# RemoteBoard.net
KiCad netlist of a schematic drawn in EAGLE
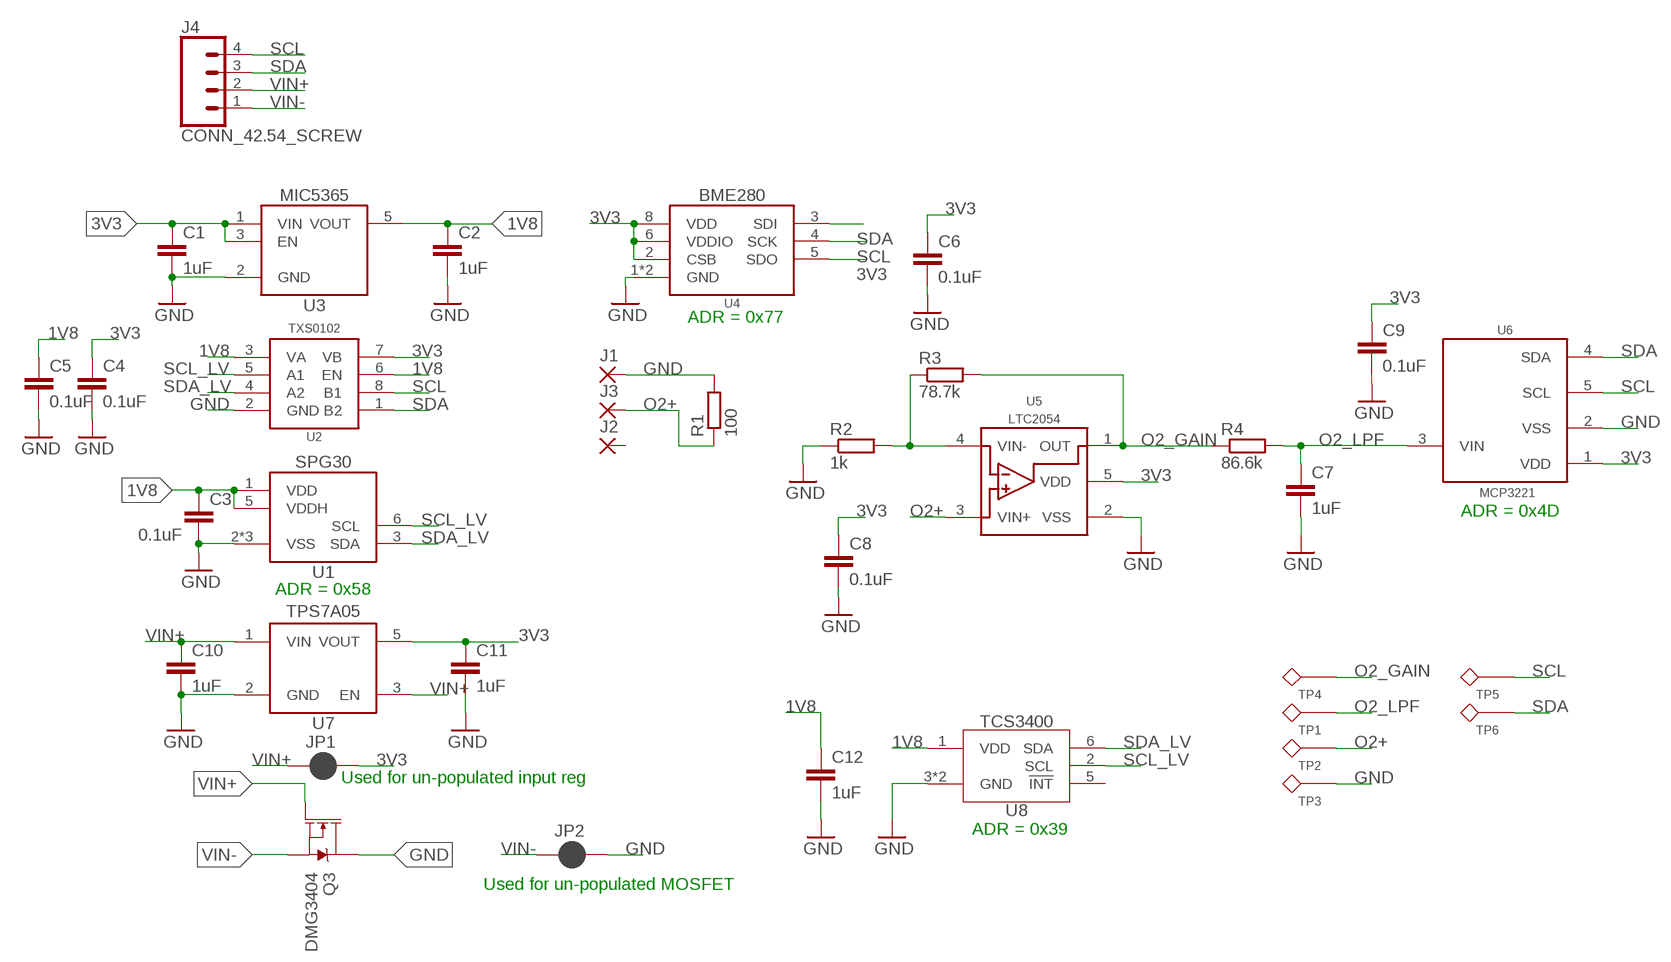
[diagram p0: schematic, sheet 1]

(export (version "E")
  (design (tool "Eeschema 10.0.6"))
  (components
    (comp (ref "C1")
      (value "1uF")
      (footprint "eagle-import:C0805")
      (fields (field (name "MF") "Yageo") (field (name "MPN") "CC0805KKX7R8BB105"))
      (libsource (lib "eagle-import") (part "C-EUC08051UF"))
    )
    (comp (ref "C2")
      (value "1uF")
      (footprint "eagle-import:C0805")
      (fields (field (name "MF") "Yageo") (field (name "MPN") "CC0805KKX7R8BB105"))
      (libsource (lib "eagle-import") (part "C-EUC08051UF"))
    )
    (comp (ref "C3")
      (value "0.1uF")
      (footprint "eagle-import:C0805")
      (fields (field (name "MF") "Kemet") (field (name "MPN") "C0805C104M3RACTU"))
      (libsource (lib "eagle-import") (part "C-EUC08050.1UF"))
    )
    (comp (ref "C4")
      (value "0.1uF")
      (footprint "eagle-import:C0805")
      (fields (field (name "MF") "Kemet") (field (name "MPN") "C0805C104M3RACTU"))
      (libsource (lib "eagle-import") (part "C-EUC08050.1UF"))
    )
    (comp (ref "C5")
      (value "0.1uF")
      (footprint "eagle-import:C0805")
      (fields (field (name "MF") "Kemet") (field (name "MPN") "C0805C104M3RACTU"))
      (libsource (lib "eagle-import") (part "C-EUC08050.1UF"))
    )
    (comp (ref "C6")
      (value "0.1uF")
      (footprint "eagle-import:C0805")
      (fields (field (name "MF") "Kemet") (field (name "MPN") "C0805C104M3RACTU"))
      (libsource (lib "eagle-import") (part "C-EUC08050.1UF"))
    )
    (comp (ref "C7")
      (value "1uF")
      (footprint "eagle-import:C0805")
      (fields (field (name "MF") "Yageo") (field (name "MPN") "CC0805KKX7R8BB105"))
      (libsource (lib "eagle-import") (part "C-EUC08051UF"))
    )
    (comp (ref "C8")
      (value "0.1uF")
      (footprint "eagle-import:C0805")
      (fields (field (name "MF") "Kemet") (field (name "MPN") "C0805C104M3RACTU"))
      (libsource (lib "eagle-import") (part "C-EUC08050.1UF"))
    )
    (comp (ref "C9")
      (value "0.1uF")
      (footprint "eagle-import:C0805")
      (fields (field (name "MF") "Kemet") (field (name "MPN") "C0805C104M3RACTU"))
      (libsource (lib "eagle-import") (part "C-EUC08050.1UF"))
    )
    (comp (ref "C10")
      (value "1uF")
      (footprint "eagle-import:C0805")
      (fields (field (name "MF") "Yageo") (field (name "MPN") "CC0805KKX7R8BB105"))
      (libsource (lib "eagle-import") (part "C-EUC08051UF"))
    )
    (comp (ref "C11")
      (value "1uF")
      (footprint "eagle-import:C0805")
      (fields (field (name "MF") "Yageo") (field (name "MPN") "CC0805KKX7R8BB105"))
      (libsource (lib "eagle-import") (part "C-EUC08051UF"))
    )
    (comp (ref "C12")
      (value "1uF")
      (footprint "eagle-import:C0805")
      (fields (field (name "MF") "Yageo") (field (name "MPN") "CC0805KKX7R8BB105"))
      (libsource (lib "eagle-import") (part "C-EUC08051UF"))
    )
    (comp (ref "J1")
      (value "SOCKETS9111_SLOT")
      (footprint "eagle-import:SOCKET_S9111-45R_SLOT")
      (fields (field (name "MF") "Harwin") (field (name "MPN") "S9111-45R"))
      (libsource (lib "eagle-import") (part "SOCKETS9111_SLOT"))
    )
    (comp (ref "J2")
      (value "SOCKETS9111_SLOT")
      (footprint "eagle-import:SOCKET_S9111-45R_SLOT")
      (fields (field (name "MF") "Harwin") (field (name "MPN") "S9111-45R"))
      (libsource (lib "eagle-import") (part "SOCKETS9111_SLOT"))
    )
    (comp (ref "J3")
      (value "SOCKETS9111_SLOT")
      (footprint "eagle-import:SOCKET_S9111-45R_SLOT")
      (fields (field (name "MF") "Harwin") (field (name "MPN") "S9111-45R"))
      (libsource (lib "eagle-import") (part "SOCKETS9111_SLOT"))
    )
    (comp (ref "J4")
      (value "CONN_42.54_SCREW")
      (footprint "eagle-import:1X04_SCREW")
      (fields (field (name "MF") "On Shore") (field (name "MPN") "OSTVN04A150"))
      (libsource (lib "eagle-import") (part "CONN_42.54_SCREW"))
    )
    (comp (ref "JP1")
      (value "JUMPER-SMT_2_NC_PASTE_SILK")
      (footprint "eagle-import:SMT-JUMPER_2_NC_PASTE_SILK")
      (libsource (lib "eagle-import") (part "JUMPER-SMT_2_NC_PASTE_SILK"))
    )
    (comp (ref "JP2")
      (value "JUMPER-SMT_2_NC_PASTE_SILK")
      (footprint "eagle-import:SMT-JUMPER_2_NC_PASTE_SILK")
      (libsource (lib "eagle-import") (part "JUMPER-SMT_2_NC_PASTE_SILK"))
    )
    (comp (ref "Q3")
      (value "DMG3404")
      (footprint "eagle-import:SOT23-3")
      (fields (field (name "MF") "Diodes Incorporated") (field (name "MPN") "DMG3404L-7"))
      (libsource (lib "eagle-import") (part "MOSFET-NCH-DMG3404L"))
    )
    (comp (ref "R1")
      (value "100")
      (footprint "eagle-import:R0805")
      (fields (field (name "MF") "Yageo") (field (name "MPN") "RC0805FR-07100RL"))
      (libsource (lib "eagle-import") (part "R-EU_R0805100"))
    )
    (comp (ref "R2")
      (value "1k")
      (footprint "eagle-import:R0805")
      (fields (field (name "MF") "Yageo") (field (name "MPN") "RC0805FR-071KL"))
      (libsource (lib "eagle-import") (part "R-EU_R08051K"))
    )
    (comp (ref "R3")
      (value "78.7k")
      (footprint "eagle-import:R0805")
      (fields (field (name "MF") "Yageo") (field (name "MPN") "RC0805FR-0778K7L"))
      (libsource (lib "eagle-import") (part "R-EU_R080578.7K"))
    )
    (comp (ref "R4")
      (value "86.6k")
      (footprint "eagle-import:R0805")
      (fields (field (name "MF") "Yageo") (field (name "MPN") "RC0805FR-0786K6L"))
      (libsource (lib "eagle-import") (part "R-EU_R080586.6K"))
    )
    (comp (ref "TP1")
      (value "TESTPOINTRCU")
      (footprint "eagle-import:TESTPOINT_0603")
      (fields (field (name "MF") "TE Connectivity") (field (name "MPN") "RCU-0C"))
      (libsource (lib "eagle-import") (part "TESTPOINTRCU"))
    )
    (comp (ref "TP2")
      (value "TESTPOINTRCU")
      (footprint "eagle-import:TESTPOINT_0603")
      (fields (field (name "MF") "TE Connectivity") (field (name "MPN") "RCU-0C"))
      (libsource (lib "eagle-import") (part "TESTPOINTRCU"))
    )
    (comp (ref "TP3")
      (value "TESTPOINTRCU")
      (footprint "eagle-import:TESTPOINT_0603")
      (fields (field (name "MF") "TE Connectivity") (field (name "MPN") "RCU-0C"))
      (libsource (lib "eagle-import") (part "TESTPOINTRCU"))
    )
    (comp (ref "TP4")
      (value "TESTPOINTRCU")
      (footprint "eagle-import:TESTPOINT_0603")
      (fields (field (name "MF") "TE Connectivity") (field (name "MPN") "RCU-0C"))
      (libsource (lib "eagle-import") (part "TESTPOINTRCU"))
    )
    (comp (ref "TP5")
      (value "TESTPOINTRCU")
      (footprint "eagle-import:TESTPOINT_0603")
      (fields (field (name "MF") "TE Connectivity") (field (name "MPN") "RCU-0C"))
      (libsource (lib "eagle-import") (part "TESTPOINTRCU"))
    )
    (comp (ref "TP6")
      (value "TESTPOINTRCU")
      (footprint "eagle-import:TESTPOINT_0603")
      (fields (field (name "MF") "TE Connectivity") (field (name "MPN") "RCU-0C"))
      (libsource (lib "eagle-import") (part "TESTPOINTRCU"))
    )
    (comp (ref "U1")
      (value "SPG30")
      (footprint "eagle-import:DFN_6_2.5X2.5")
      (fields (field (name "MF") "Sensirion") (field (name "MPN") "SGP30-2.5K"))
      (libsource (lib "eagle-import") (part "SPG30"))
    )
    (comp (ref "U2")
      (value "TXS0102DCU")
      (footprint "eagle-import:DCU_(R-PDSO-G8)")
      (fields (field (name "MF") "TI") (field (name "MPN") "TXS0102DCUR"))
      (libsource (lib "eagle-import") (part "TXS0102DCU"))
    )
    (comp (ref "U3")
      (value "MIC53651.8SC70")
      (footprint "eagle-import:DCK_R-PDSO-G5")
      (fields (field (name "MF") "Microchip") (field (name "MPN") "MIC5365-1.8YC5-TR"))
      (libsource (lib "eagle-import") (part "MIC5365SC701.8"))
    )
    (comp (ref "U4")
      (value "BME280")
      (footprint "eagle-import:BME280")
      (fields (field (name "DISP") "BME280") (field (name "MF") "Bosch"))
      (libsource (lib "eagle-import") (part "BME280"))
    )
    (comp (ref "U5")
      (value "LTC2054")
      (footprint "eagle-import:SOT23-5")
      (fields
        (field (name "DISP") "LTC2054")
        (field (name "MF") "LT")
        (field (name "MPN") "LTC2054HS5#TRMPBF")
      )
      (libsource (lib "eagle-import") (part "LTC2054"))
    )
    (comp (ref "U6")
      (value "MCP3221")
      (footprint "eagle-import:SOT23-5")
      (fields (field (name "DISP") "MCP3221") (field (name "MF") "TI") (field (name "MPN") "MCP3221A5T-I/OT"))
      (libsource (lib "eagle-import") (part "MCP3221"))
    )
    (comp (ref "U7")
      (value "TPS7A0533DBV")
      (footprint "eagle-import:SOT23-5")
      (fields (field (name "MF") "TI") (field (name "MPN") "TPS7A0533PDBVR"))
      (libsource (lib "eagle-import") (part "TPS7A05DBV33"))
    )
    (comp (ref "U8")
      (value "TCS3400")
      (footprint "eagle-import:TCS3400")
      (fields (field (name "MF") "AMS") (field (name "MPN") "TCS34003FNM"))
      (libsource (lib "eagle-import") (part "TCS3400"))
    )
  )
  (nets
    (net (code "1") (name "/O2+") (class "Default")
      (node (ref "J3") (pin "PAD") (pinfunction "P_PAD") (pintype "passive"))
      (node (ref "R1") (pin "1") (pinfunction "1_1") (pintype "passive"))
      (node (ref "TP2") (pin "1") (pinfunction "P$1_1") (pintype "bidirectional"))
      (node (ref "U5") (pin "3") (pinfunction "VIN+_3") (pintype "input"))
    )
    (net (code "2") (name "/O2_GAIN") (class "Default")
      (node (ref "R3") (pin "2") (pinfunction "2_2") (pintype "passive"))
      (node (ref "R4") (pin "1") (pinfunction "1_1") (pintype "passive"))
      (node (ref "TP4") (pin "1") (pinfunction "P$1_1") (pintype "bidirectional"))
      (node (ref "U5") (pin "1") (pinfunction "OUT_1") (pintype "output"))
    )
    (net (code "3") (name "/O2_LPF") (class "Default")
      (node (ref "C7") (pin "1") (pinfunction "1_1") (pintype "passive"))
      (node (ref "R4") (pin "2") (pinfunction "2_2") (pintype "passive"))
      (node (ref "TP1") (pin "1") (pinfunction "P$1_1") (pintype "bidirectional"))
      (node (ref "U6") (pin "3") (pinfunction "VIN_3") (pintype "input"))
    )
    (net (code "4") (name "/SCL") (class "Default")
      (node (ref "J4") (pin "4") (pinfunction "4_4") (pintype "passive"))
      (node (ref "TP5") (pin "1") (pinfunction "P$1_1") (pintype "bidirectional"))
      (node (ref "U2") (pin "8") (pinfunction "B1_8") (pintype "bidirectional"))
      (node (ref "U4") (pin "4") (pinfunction "SCK_4") (pintype "bidirectional"))
      (node (ref "U6") (pin "5") (pinfunction "SCL_5") (pintype "bidirectional"))
    )
    (net (code "5") (name "/SCL_LV") (class "Default")
      (node (ref "U1") (pin "6") (pinfunction "SCL_6") (pintype "input"))
      (node (ref "U2") (pin "5") (pinfunction "A1_5") (pintype "bidirectional"))
      (node (ref "U8") (pin "2") (pinfunction "SCL_2") (pintype "input"))
    )
    (net (code "6") (name "/SDA") (class "Default")
      (node (ref "J4") (pin "3") (pinfunction "3_3") (pintype "passive"))
      (node (ref "TP6") (pin "1") (pinfunction "P$1_1") (pintype "bidirectional"))
      (node (ref "U2") (pin "1") (pinfunction "B2_1") (pintype "bidirectional"))
      (node (ref "U4") (pin "3") (pinfunction "SDI_3") (pintype "bidirectional"))
      (node (ref "U6") (pin "4") (pinfunction "SDA_4") (pintype "bidirectional"))
    )
    (net (code "7") (name "/SDA_LV") (class "Default")
      (node (ref "U1") (pin "3") (pinfunction "SDA_3") (pintype "bidirectional"))
      (node (ref "U2") (pin "4") (pinfunction "A2_4") (pintype "bidirectional"))
      (node (ref "U8") (pin "6") (pinfunction "SDA_6") (pintype "bidirectional"))
    )
    (net (code "8") (name "1V8") (class "Default")
      (node (ref "C12") (pin "1") (pinfunction "1_1") (pintype "passive"))
      (node (ref "C2") (pin "1") (pinfunction "1_1") (pintype "passive"))
      (node (ref "C3") (pin "1") (pinfunction "1_1") (pintype "passive"))
      (node (ref "C5") (pin "1") (pinfunction "1_1") (pintype "passive"))
      (node (ref "U1") (pin "1") (pinfunction "VDD_1") (pintype "power_in"))
      (node (ref "U1") (pin "5") (pinfunction "VDDH_5") (pintype "power_in"))
      (node (ref "U2") (pin "3") (pinfunction "VA_3") (pintype "power_in"))
      (node (ref "U2") (pin "6") (pinfunction "EN_6") (pintype "input"))
      (node (ref "U3") (pin "5") (pinfunction "VOUT_5") (pintype "power_in"))
      (node (ref "U8") (pin "1") (pinfunction "VDD_1") (pintype "power_in"))
    )
    (net (code "9") (name "3V3") (class "Default")
      (node (ref "C1") (pin "1") (pinfunction "1_1") (pintype "passive"))
      (node (ref "C11") (pin "1") (pinfunction "1_1") (pintype "passive"))
      (node (ref "C4") (pin "1") (pinfunction "1_1") (pintype "passive"))
      (node (ref "C6") (pin "1") (pinfunction "1_1") (pintype "passive"))
      (node (ref "C8") (pin "1") (pinfunction "1_1") (pintype "passive"))
      (node (ref "C9") (pin "1") (pinfunction "1_1") (pintype "passive"))
      (node (ref "JP1") (pin "2") (pinfunction "2_2") (pintype "passive"))
      (node (ref "U2") (pin "7") (pinfunction "VB_7") (pintype "power_in"))
      (node (ref "U3") (pin "1") (pinfunction "VIN_1") (pintype "power_in"))
      (node (ref "U3") (pin "3") (pinfunction "EN_3") (pintype "input"))
      (node (ref "U4") (pin "2") (pinfunction "CSB_2") (pintype "bidirectional"))
      (node (ref "U4") (pin "5") (pinfunction "SDO_5") (pintype "bidirectional"))
      (node (ref "U4") (pin "6") (pinfunction "VDDIO_6") (pintype "bidirectional"))
      (node (ref "U4") (pin "8") (pinfunction "VDD_8") (pintype "power_in"))
      (node (ref "U5") (pin "5") (pinfunction "VDD_5") (pintype "power_in"))
      (node (ref "U6") (pin "1") (pinfunction "VDD_1") (pintype "power_in"))
      (node (ref "U7") (pin "5") (pinfunction "VOUT_5") (pintype "power_in"))
    )
    (net (code "10") (name "GND") (class "Default")
      (node (ref "C1") (pin "2") (pinfunction "2_2") (pintype "passive"))
      (node (ref "C10") (pin "2") (pinfunction "2_2") (pintype "passive"))
      (node (ref "C11") (pin "2") (pinfunction "2_2") (pintype "passive"))
      (node (ref "C12") (pin "2") (pinfunction "2_2") (pintype "passive"))
      (node (ref "C2") (pin "2") (pinfunction "2_2") (pintype "passive"))
      (node (ref "C3") (pin "2") (pinfunction "2_2") (pintype "passive"))
      (node (ref "C4") (pin "2") (pinfunction "2_2") (pintype "passive"))
      (node (ref "C5") (pin "2") (pinfunction "2_2") (pintype "passive"))
      (node (ref "C6") (pin "2") (pinfunction "2_2") (pintype "passive"))
      (node (ref "C7") (pin "2") (pinfunction "2_2") (pintype "passive"))
      (node (ref "C8") (pin "2") (pinfunction "2_2") (pintype "passive"))
      (node (ref "C9") (pin "2") (pinfunction "2_2") (pintype "passive"))
      (node (ref "J1") (pin "PAD") (pinfunction "P_PAD") (pintype "passive"))
      (node (ref "JP2") (pin "2") (pinfunction "2_2") (pintype "passive"))
      (node (ref "Q3") (pin "3") (pinfunction "D_3") (pintype "bidirectional"))
      (node (ref "R1") (pin "2") (pinfunction "2_2") (pintype "passive"))
      (node (ref "R2") (pin "1") (pinfunction "1_1") (pintype "passive"))
      (node (ref "TP3") (pin "1") (pinfunction "P$1_1") (pintype "bidirectional"))
      (node (ref "U1") (pin "2") (pinfunction "VSS_2") (pintype "power_in"))
      (node (ref "U1") (pin "4") (pinfunction "VSS_4") (pintype "power_in"))
      (node (ref "U1") (pin "EP") (pinfunction "VSS_EP") (pintype "power_in"))
      (node (ref "U2") (pin "2") (pinfunction "GND_2") (pintype "power_in"))
      (node (ref "U3") (pin "2") (pinfunction "GND_2") (pintype "power_in"))
      (node (ref "U4") (pin "1") (pinfunction "GND_1") (pintype "power_in"))
      (node (ref "U4") (pin "7") (pinfunction "GND_7") (pintype "power_in"))
      (node (ref "U5") (pin "2") (pinfunction "VSS_2") (pintype "power_in"))
      (node (ref "U6") (pin "2") (pinfunction "VSS_2") (pintype "power_in"))
      (node (ref "U7") (pin "2") (pinfunction "GND_2") (pintype "power_in"))
      (node (ref "U8") (pin "3") (pinfunction "GND_3") (pintype "power_in"))
      (node (ref "U8") (pin "4") (pinfunction "GND_4") (pintype "power_in"))
    )
    (net (code "11") (name "Net-(U5-VIN-)") (class "Default")
      (node (ref "R2") (pin "2") (pinfunction "2_2") (pintype "passive"))
      (node (ref "R3") (pin "1") (pinfunction "1_1") (pintype "passive"))
      (node (ref "U5") (pin "4") (pinfunction "VIN-_4") (pintype "input"))
    )
    (net (code "12") (name "VIN+") (class "Default")
      (node (ref "C10") (pin "1") (pinfunction "1_1") (pintype "passive"))
      (node (ref "J4") (pin "2") (pinfunction "2_2") (pintype "passive"))
      (node (ref "JP1") (pin "1") (pinfunction "1_1") (pintype "passive"))
      (node (ref "Q3") (pin "1") (pinfunction "G_1") (pintype "bidirectional"))
      (node (ref "U7") (pin "1") (pinfunction "VIN_1") (pintype "power_in"))
      (node (ref "U7") (pin "3") (pinfunction "EN_3") (pintype "input"))
    )
    (net (code "13") (name "VIN-") (class "Default")
      (node (ref "J4") (pin "1") (pinfunction "1_1") (pintype "passive"))
      (node (ref "JP2") (pin "1") (pinfunction "1_1") (pintype "passive"))
      (node (ref "Q3") (pin "2") (pinfunction "S_2") (pintype "bidirectional"))
    )
    (net (code "14") (name "unconnected-(J2-P-PadPAD)") (class "Default")
      (node (ref "J2") (pin "PAD") (pinfunction "P_PAD") (pintype "passive"))
    )
    (net (code "15") (name "unconnected-(U8-~{INT}-Pad5)") (class "Default")
      (node (ref "U8") (pin "5") (pinfunction "~{INT}_5") (pintype "output"))
    )
  )
)
